# N2a.net
KiCad netlist of a schematic drawn in EAGLE
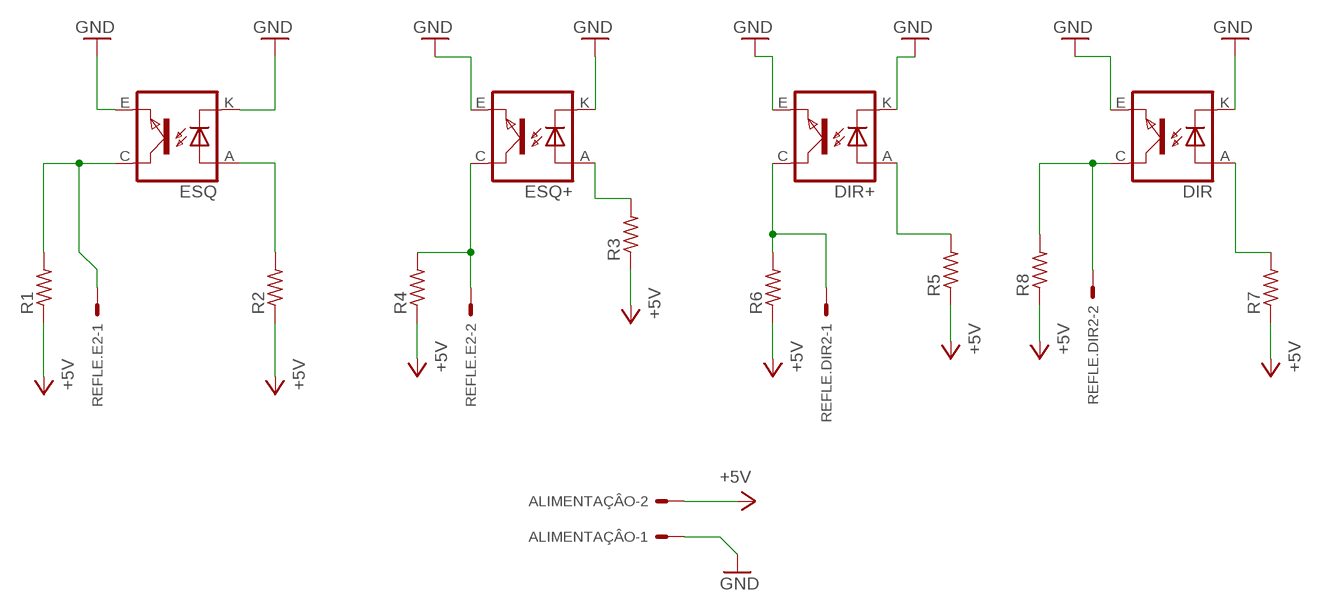
[diagram p0: schematic, sheet 1]

(export (version "E")
  (design (tool "Eeschema 10.0.6"))
  (components
    (comp (ref "ALIMENTAÇÂO")
      (value "CONN_0205-7028")
      (footprint "eagle-import:7395-02")
      (libsource (lib "eagle-import") (part "CONN_0205-7028"))
    )
    (comp (ref "DIR")
      (value "TCRT5000")
      (footprint "eagle-import:TCRT5000")
      (libsource (lib "eagle-import") (part "TCRT5000"))
    )
    (comp (ref "DIR+")
      (value "TCRT5000")
      (footprint "eagle-import:TCRT5000")
      (libsource (lib "eagle-import") (part "TCRT5000"))
    )
    (comp (ref "ESQ")
      (value "TCRT5000")
      (footprint "eagle-import:TCRT5000")
      (libsource (lib "eagle-import") (part "TCRT5000"))
    )
    (comp (ref "ESQ+")
      (value "TCRT5000")
      (footprint "eagle-import:TCRT5000")
      (libsource (lib "eagle-import") (part "TCRT5000"))
    )
    (comp (ref "R1")
      (value "R-US_0204/7")
      (footprint "eagle-import:0204_7")
      (libsource (lib "eagle-import") (part "R-US_0204/7"))
    )
    (comp (ref "R2")
      (value "R-US_0204/7")
      (footprint "eagle-import:0204_7")
      (libsource (lib "eagle-import") (part "R-US_0204/7"))
    )
    (comp (ref "R3")
      (value "R-US_0204/7")
      (footprint "eagle-import:0204_7")
      (libsource (lib "eagle-import") (part "R-US_0204/7"))
    )
    (comp (ref "R4")
      (value "R-US_0204/7")
      (footprint "eagle-import:0204_7")
      (libsource (lib "eagle-import") (part "R-US_0204/7"))
    )
    (comp (ref "R5")
      (value "R-US_0204/7")
      (footprint "eagle-import:0204_7")
      (libsource (lib "eagle-import") (part "R-US_0204/7"))
    )
    (comp (ref "R6")
      (value "R-US_0204/7")
      (footprint "eagle-import:0204_7")
      (libsource (lib "eagle-import") (part "R-US_0204/7"))
    )
    (comp (ref "R7")
      (value "R-US_0204/7")
      (footprint "eagle-import:0204_7")
      (libsource (lib "eagle-import") (part "R-US_0204/7"))
    )
    (comp (ref "R8")
      (value "R-US_0204/7")
      (footprint "eagle-import:0204_7")
      (libsource (lib "eagle-import") (part "R-US_0204/7"))
    )
    (comp (ref "REFLE.DIR2")
      (value "CONN_0205-7028")
      (footprint "eagle-import:7395-02")
      (libsource (lib "eagle-import") (part "CONN_0205-7028"))
    )
    (comp (ref "REFLE.E2")
      (value "CONN_0205-7028")
      (footprint "eagle-import:7395-02")
      (libsource (lib "eagle-import") (part "CONN_0205-7028"))
    )
  )
  (nets
    (net (code "1") (name "+5V") (class "Default")
      (node (ref "ALIMENTAÇÂO") (pin "2") (pinfunction "S_2") (pintype "passive"))
      (node (ref "R1") (pin "1") (pinfunction "1_1") (pintype "passive"))
      (node (ref "R2") (pin "1") (pinfunction "1_1") (pintype "passive"))
      (node (ref "R3") (pin "1") (pinfunction "1_1") (pintype "passive"))
      (node (ref "R4") (pin "1") (pinfunction "1_1") (pintype "passive"))
      (node (ref "R5") (pin "1") (pinfunction "1_1") (pintype "passive"))
      (node (ref "R6") (pin "1") (pinfunction "1_1") (pintype "passive"))
      (node (ref "R7") (pin "1") (pinfunction "1_1") (pintype "passive"))
      (node (ref "R8") (pin "1") (pinfunction "1_1") (pintype "passive"))
    )
    (net (code "2") (name "GND") (class "Default")
      (node (ref "ALIMENTAÇÂO") (pin "1") (pinfunction "S_1") (pintype "passive"))
      (node (ref "DIR") (pin "E") (pinfunction "EMITTER_E") (pintype "passive"))
      (node (ref "DIR") (pin "K") (pinfunction "CATHODE_K") (pintype "passive"))
      (node (ref "DIR+") (pin "E") (pinfunction "EMITTER_E") (pintype "passive"))
      (node (ref "DIR+") (pin "K") (pinfunction "CATHODE_K") (pintype "passive"))
      (node (ref "ESQ") (pin "E") (pinfunction "EMITTER_E") (pintype "passive"))
      (node (ref "ESQ") (pin "K") (pinfunction "CATHODE_K") (pintype "passive"))
      (node (ref "ESQ+") (pin "E") (pinfunction "EMITTER_E") (pintype "passive"))
      (node (ref "ESQ+") (pin "K") (pinfunction "CATHODE_K") (pintype "passive"))
    )
    (net (code "3") (name "Net-(DIR+-ANODE)") (class "Default")
      (node (ref "DIR+") (pin "A") (pinfunction "ANODE_A") (pintype "passive"))
      (node (ref "R5") (pin "2") (pinfunction "2_2") (pintype "passive"))
    )
    (net (code "4") (name "Net-(DIR+-COLLECTOR)") (class "Default")
      (node (ref "DIR+") (pin "C") (pinfunction "COLLECTOR_C") (pintype "passive"))
      (node (ref "R6") (pin "2") (pinfunction "2_2") (pintype "passive"))
      (node (ref "REFLE.DIR2") (pin "1") (pinfunction "S_1") (pintype "passive"))
    )
    (net (code "5") (name "Net-(DIR-ANODE)") (class "Default")
      (node (ref "DIR") (pin "A") (pinfunction "ANODE_A") (pintype "passive"))
      (node (ref "R7") (pin "2") (pinfunction "2_2") (pintype "passive"))
    )
    (net (code "6") (name "Net-(DIR-COLLECTOR)") (class "Default")
      (node (ref "DIR") (pin "C") (pinfunction "COLLECTOR_C") (pintype "passive"))
      (node (ref "R8") (pin "2") (pinfunction "2_2") (pintype "passive"))
      (node (ref "REFLE.DIR2") (pin "2") (pinfunction "S_2") (pintype "passive"))
    )
    (net (code "7") (name "Net-(ESQ+-ANODE)") (class "Default")
      (node (ref "ESQ+") (pin "A") (pinfunction "ANODE_A") (pintype "passive"))
      (node (ref "R3") (pin "2") (pinfunction "2_2") (pintype "passive"))
    )
    (net (code "8") (name "Net-(ESQ+-COLLECTOR)") (class "Default")
      (node (ref "ESQ+") (pin "C") (pinfunction "COLLECTOR_C") (pintype "passive"))
      (node (ref "R4") (pin "2") (pinfunction "2_2") (pintype "passive"))
      (node (ref "REFLE.E2") (pin "2") (pinfunction "S_2") (pintype "passive"))
    )
    (net (code "9") (name "Net-(ESQ-ANODE)") (class "Default")
      (node (ref "ESQ") (pin "A") (pinfunction "ANODE_A") (pintype "passive"))
      (node (ref "R2") (pin "2") (pinfunction "2_2") (pintype "passive"))
    )
    (net (code "10") (name "Net-(ESQ-COLLECTOR)") (class "Default")
      (node (ref "ESQ") (pin "C") (pinfunction "COLLECTOR_C") (pintype "passive"))
      (node (ref "R1") (pin "2") (pinfunction "2_2") (pintype "passive"))
      (node (ref "REFLE.E2") (pin "1") (pinfunction "S_1") (pintype "passive"))
    )
  )
)
